# 3v3_power.net
KiCad netlist of a schematic drawn in Altium Designer
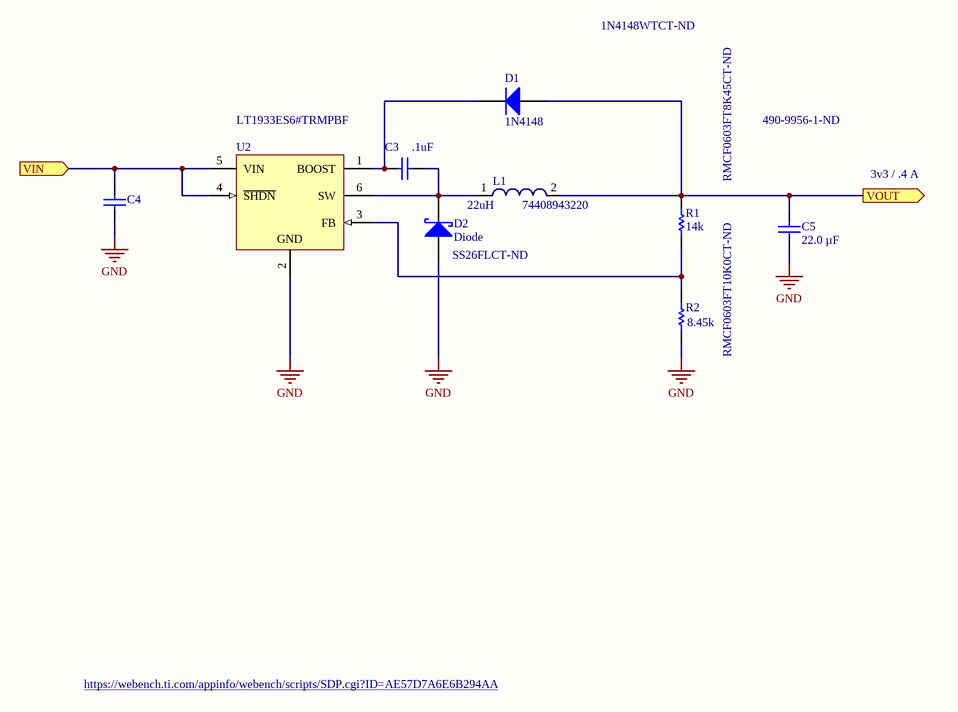
[diagram p0: 3v3_power.SchDoc]

(export (version "E")
  (design (tool "Eeschema 10.0.6"))
  (components
    (comp (ref "C3")
      (value "Murata GRM21BR71H104KA01L")
      (footprint "CAPC2013X135X45LL10T25")
      (description "Capacitor 10% GRM21BR71H104KA01/GRM21BR71H104KA01L MURATA RoHS Micro Farad=0.1 V=50 SO0805")
      (fields
        (field (name "MANUFACTURER PART NUMBER") "GRM21BR71H104KA01L")
        (field (name "CAPACITANCE") ".1uF")
      )
      (libsource (lib "CommunityVault") (part "CMP-db42124a01380485-1"))
    )
    (comp (ref "C4")
      (value "Murata GRM21BC8YA225KA73L")
      (footprint "CAPC2013X140X45ML15T25")
      (description "MURATA   GRM21BC8YA225KA73L   CAP, MLCC, X6S, 2.2UF, 35V, 0805")
      (libsource (lib "CommunityVault") (part "CMP-3979846-2"))
    )
    (comp (ref "C5")
      (value "SYM-de6015a2879501a7-1")
      (footprint "PCB-zk3e6ylmsz65xxlgquxh-1")
      (description "Cap Ceramic 22uF 16V X6S 20% SMD 0805 105°C Embossed T/R")
      (fields (field (name "CAPACITANCE") "22.0 µF"))
      (libsource (lib "CommunityVault") (part "CMP-de6015a2879501a7-1"))
    )
    (comp (ref "D1")
      (value "1N4148")
      (footprint "PCB-1N4148W-7-F")
      (description "Fast Switching Diode, 100V, 400mW, Surface Mount, SOD-123")
      (fields (field (name "MANUFACTURER PART NUMBER") "1N4148W-7-F"))
      (libsource (lib "CommunityVault") (part "1N4148"))
    )
    (comp (ref "D2")
      (value "Diode")
      (footprint "PCB-5gde02dk4bufsuch8kid-1")
      (description "Diode Schottky Barrier Rectifier 60V 2A 2-Pin SOD-123F T/R")
      (libsource (lib "CommunityVault") (part "SYM-0675ccf66d19d9b2-1"))
    )
    (comp (ref "L1")
      (value "74408943220")
      (footprint "WE-SPC 4838")
      (description "SMD Shielded Power Inductor WE-SPC, L=22 µH")
      (fields (field (name "INDUCTANCE") "22uH"))
      (libsource (lib "CommunityVault") (part "CMP-915955-2"))
    )
    (comp (ref "R1")
      (value "Stackpole Electronics RMCF0603FT8K45")
      (footprint "PCB-9ahxsq8gddjqcnfjmojj-1")
      (fields (field (name "MANUFACTURER PART NUMBER") "RMCF0603FT8K45") (field (name "RESISTANCE") "14k"))
      (libsource (lib "CommunityVault") (part "CMP-89084127803b56cf-1"))
    )
    (comp (ref "R2")
      (value "Stackpole Electronics RMCF0603FT14K0")
      (footprint "PCB-9ahxsq8gddjqcnfjmojj-1")
      (description "Res Thick Film 0603 14K Ohm 1% 0.1W(1/10W) }100ppm/ Molded SMD Automotive T/R")
      (fields (field (name "MANUFACTURER PART NUMBER") "RMCF0603FT14K0") (field (name "RESISTANCE") "8.45k"))
      (libsource (lib "CommunityVault") (part "CMP-c96e0141c6a016a9-1"))
    )
    (comp (ref "U2")
      (value "LT1933ES6#TRMPBF")
      (footprint "LT-S6-6-SOT-23_L")
      (libsource (lib "CommunityVault") (part "CMP-1482538-2"))
    )
  )
  (nets
    (net (code "1") (name "/VIN") (class "Default")
      (node (ref "C4") (pin "1") (pinfunction "1_1") (pintype "passive"))
      (node (ref "U2") (pin "4") (pinfunction "~{SHDN}_4") (pintype "input"))
      (node (ref "U2") (pin "5") (pinfunction "VIN_5") (pintype "power_in"))
    )
    (net (code "2") (name "/VOUT") (class "Default")
      (node (ref "C5") (pin "2") (pinfunction "2_2") (pintype "passive"))
      (node (ref "D1") (pin "1") (pinfunction "A_1") (pintype "passive"))
      (node (ref "L1") (pin "2") (pinfunction "2_2") (pintype "passive"))
      (node (ref "R1") (pin "1") (pinfunction "1_1") (pintype "passive"))
    )
    (net (code "3") (name "GND") (class "Default")
      (node (ref "C4") (pin "2") (pinfunction "2_2") (pintype "passive"))
      (node (ref "C5") (pin "1") (pinfunction "1_1") (pintype "passive"))
      (node (ref "D2") (pin "1") (pinfunction "A_1") (pintype "passive"))
      (node (ref "R2") (pin "1") (pinfunction "1_1") (pintype "passive"))
      (node (ref "U2") (pin "2") (pinfunction "GND_2") (pintype "power_in"))
    )
    (net (code "4") (name "Net-(D1-K)") (class "Default")
      (node (ref "C3") (pin "1") (pinfunction "1_1") (pintype "passive"))
      (node (ref "D1") (pin "2") (pinfunction "K_2") (pintype "passive"))
      (node (ref "U2") (pin "1") (pinfunction "BOOST_1") (pintype "passive"))
    )
    (net (code "5") (name "Net-(D2-K)") (class "Default")
      (node (ref "C3") (pin "2") (pinfunction "2_2") (pintype "passive"))
      (node (ref "D2") (pin "2") (pinfunction "K_2") (pintype "passive"))
      (node (ref "L1") (pin "1") (pinfunction "1_1") (pintype "passive"))
      (node (ref "U2") (pin "6") (pinfunction "SW_6") (pintype "power_in"))
    )
    (net (code "6") (name "Net-(U2-FB)") (class "Default")
      (node (ref "R1") (pin "2") (pinfunction "2_2") (pintype "passive"))
      (node (ref "R2") (pin "2") (pinfunction "2_2") (pintype "passive"))
      (node (ref "U2") (pin "3") (pinfunction "FB_3") (pintype "input"))
    )
  )
)
